# TiltyDuo.net
KiCad netlist of a schematic drawn in EAGLE
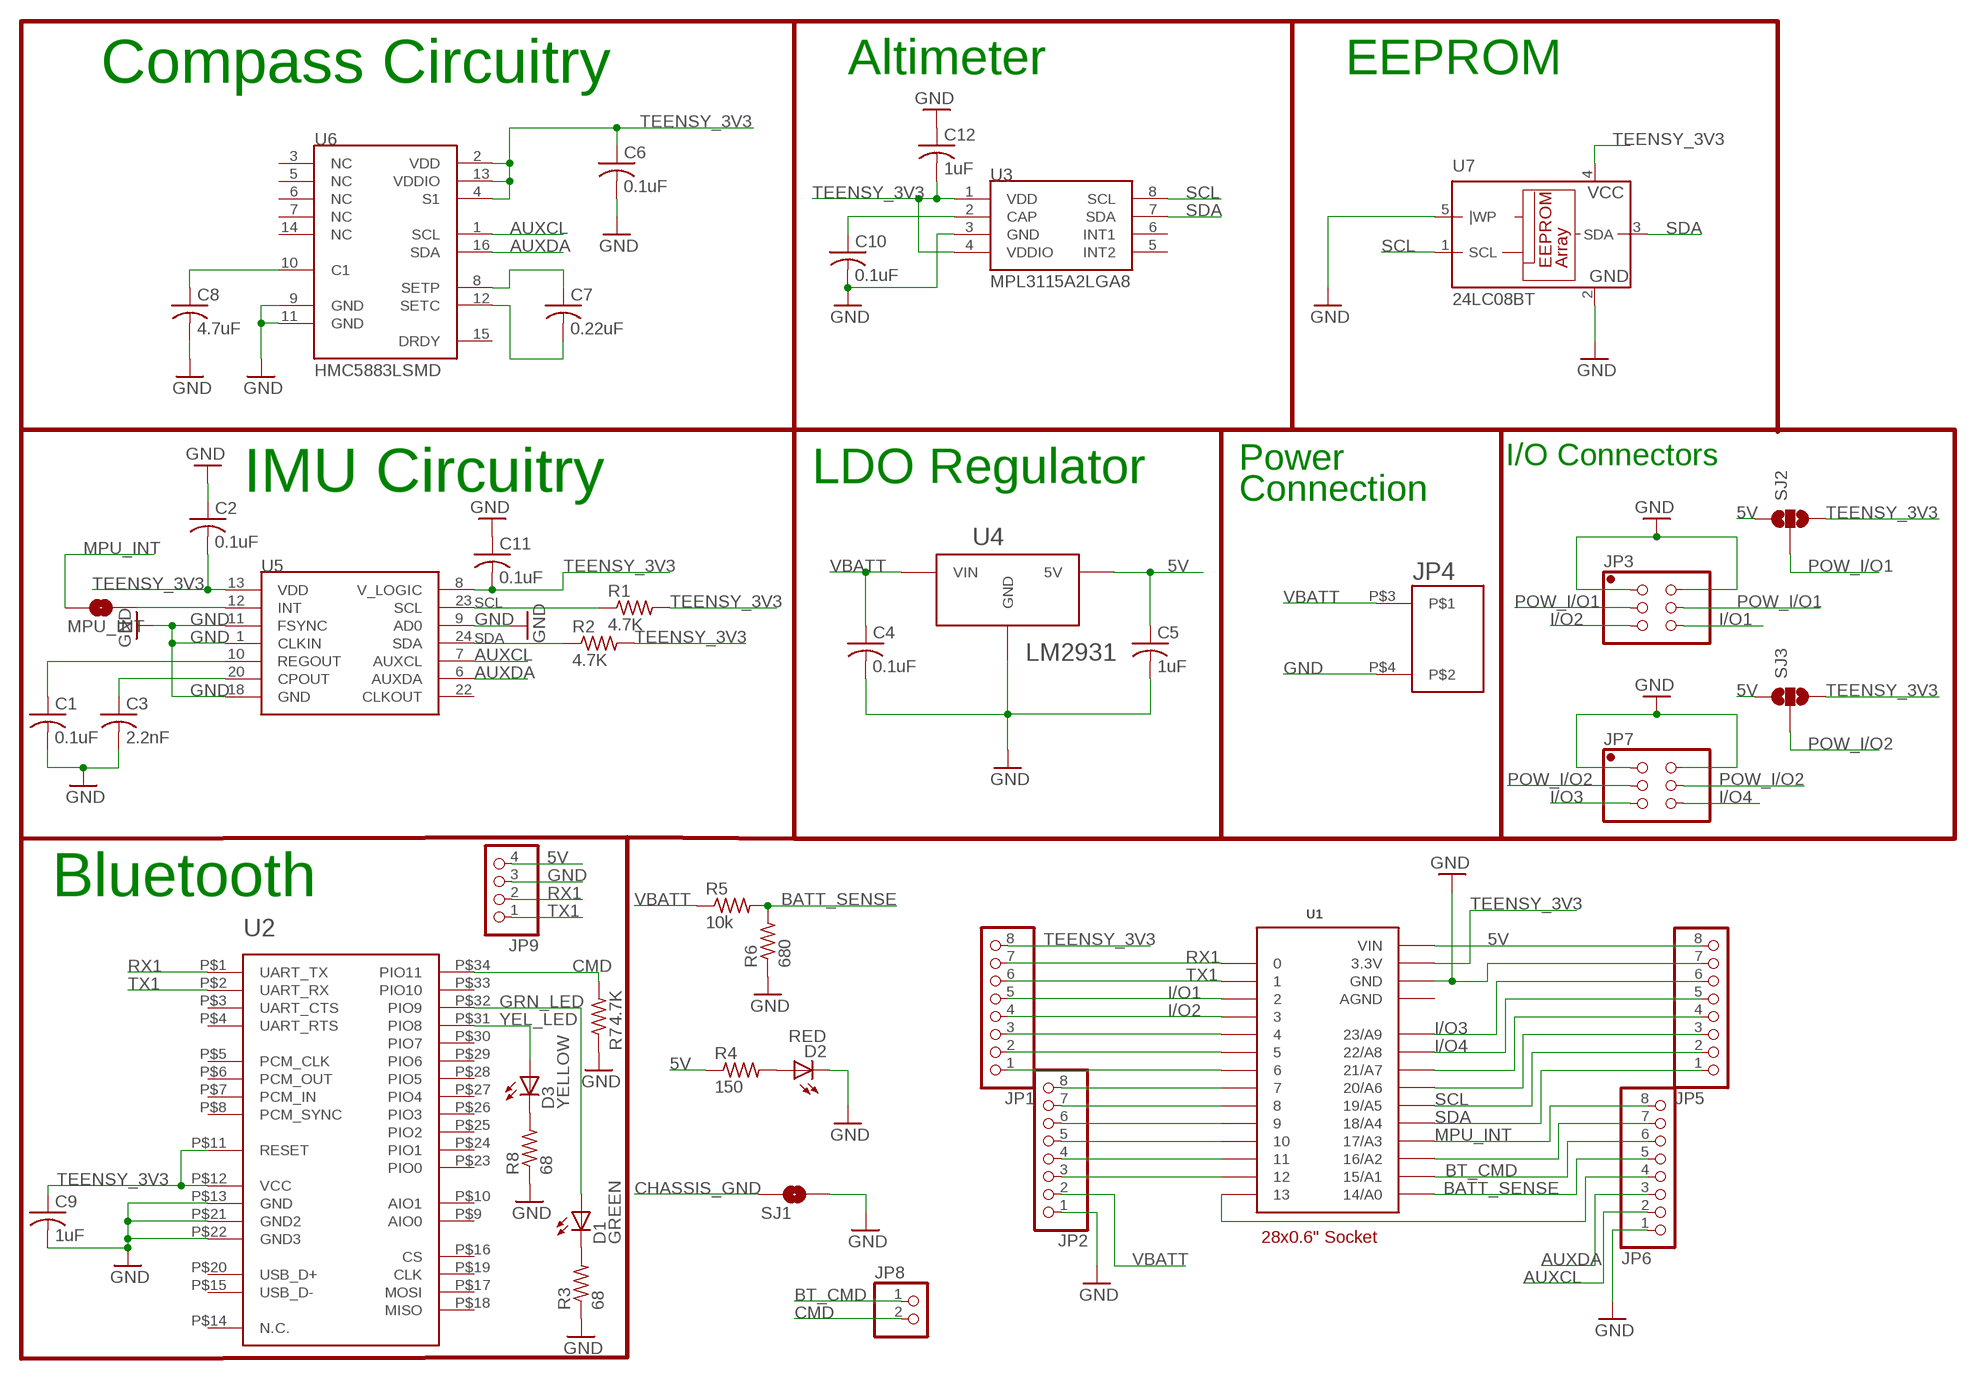
[diagram p0: schematic, sheet 1]

(export (version "E")
  (design (tool "Eeschema 10.0.6"))
  (components
    (comp (ref "C1")
      (value "0.1uF")
      (footprint "eagle-import:C0603")
      (libsource (lib "eagle-import") (part "C-USC0603"))
    )
    (comp (ref "C2")
      (value "0.1uF")
      (footprint "eagle-import:C0603")
      (libsource (lib "eagle-import") (part "C-USC0603"))
    )
    (comp (ref "C3")
      (value "2.2nF")
      (footprint "eagle-import:C0603")
      (libsource (lib "eagle-import") (part "C-USC0603"))
    )
    (comp (ref "C4")
      (value "0.1uF")
      (footprint "eagle-import:C0603")
      (libsource (lib "eagle-import") (part "C-USC0603"))
    )
    (comp (ref "C5")
      (value "1uF")
      (footprint "eagle-import:C0603")
      (libsource (lib "eagle-import") (part "C-USC0603"))
    )
    (comp (ref "C6")
      (value "0.1uF")
      (footprint "eagle-import:C0603")
      (libsource (lib "eagle-import") (part "C-USC0603"))
    )
    (comp (ref "C7")
      (value "0.22uF")
      (footprint "eagle-import:C0603")
      (libsource (lib "eagle-import") (part "C-USC0603"))
    )
    (comp (ref "C8")
      (value "4.7uF")
      (footprint "eagle-import:C0603")
      (libsource (lib "eagle-import") (part "C-USC0603"))
    )
    (comp (ref "C9")
      (value "1uF")
      (footprint "eagle-import:C0603")
      (libsource (lib "eagle-import") (part "C-USC0603"))
    )
    (comp (ref "C10")
      (value "0.1uF")
      (footprint "eagle-import:C0603")
      (libsource (lib "eagle-import") (part "C-USC0603"))
    )
    (comp (ref "C11")
      (value "0.1uF")
      (footprint "eagle-import:C0603")
      (libsource (lib "eagle-import") (part "C-USC0603"))
    )
    (comp (ref "C12")
      (value "1uF")
      (footprint "eagle-import:C0603")
      (libsource (lib "eagle-import") (part "C-USC0603"))
    )
    (comp (ref "D1")
      (value "GREEN")
      (footprint "eagle-import:LED-0805")
      (libsource (lib "eagle-import") (part "LED-GREENLED-0805_NO_SILK"))
    )
    (comp (ref "D2")
      (value "RED")
      (footprint "eagle-import:LED-0805")
      (libsource (lib "eagle-import") (part "LED-GREENLED-0805_NO_SILK"))
    )
    (comp (ref "D3")
      (value "YELLOW")
      (footprint "eagle-import:LED-0805")
      (libsource (lib "eagle-import") (part "LED-GREENLED-0805_NO_SILK"))
    )
    (comp (ref "JP1")
      (value "PINHD-1X81X08_NO_SILK")
      (footprint "eagle-import:1X08_NO_SS")
      (libsource (lib "eagle-import") (part "PINHD-1X81X08_NO_SILK"))
    )
    (comp (ref "JP2")
      (value "PINHD-1X81X08_NO_SILK")
      (footprint "eagle-import:1X08_NO_SS")
      (libsource (lib "eagle-import") (part "PINHD-1X81X08_NO_SILK"))
    )
    (comp (ref "JP3")
      (value "PINHD-2X32X03_NO_SILK")
      (footprint "eagle-import:2X03_NO_SS")
      (libsource (lib "eagle-import") (part "PINHD-2X32X03_NO_SILK"))
    )
    (comp (ref "JP4")
      (value "2-POS_SMD_TERM_BLOCK")
      (footprint "eagle-import:2-POS_SMD_TERMINAL_BLOCK")
      (libsource (lib "eagle-import") (part "2-POS_SMD_TERM_BLOCK"))
    )
    (comp (ref "JP5")
      (value "PINHD-1X81X08_NO_SILK")
      (footprint "eagle-import:1X08_NO_SS")
      (libsource (lib "eagle-import") (part "PINHD-1X81X08_NO_SILK"))
    )
    (comp (ref "JP6")
      (value "PINHD-1X81X08_NO_SILK")
      (footprint "eagle-import:1X08_NO_SS")
      (libsource (lib "eagle-import") (part "PINHD-1X81X08_NO_SILK"))
    )
    (comp (ref "JP7")
      (value "PINHD-2X32X03_NO_SILK")
      (footprint "eagle-import:2X03_NO_SS")
      (libsource (lib "eagle-import") (part "PINHD-2X32X03_NO_SILK"))
    )
    (comp (ref "JP8")
      (value "PINHD-1X21X02_NO_SILK")
      (footprint "eagle-import:1X02_NO_SS")
      (libsource (lib "eagle-import") (part "PINHD-1X21X02_NO_SILK"))
    )
    (comp (ref "JP9")
      (value "PINHD-1X4")
      (footprint "eagle-import:1X04")
      (libsource (lib "eagle-import") (part "PINHD-1X4"))
    )
    (comp (ref "MPU_INT")
      (value "SOLDERJUMPERNO")
      (footprint "eagle-import:SJ_2S-NO")
      (libsource (lib "eagle-import") (part "SOLDERJUMPERNO"))
    )
    (comp (ref "R1")
      (value "4.7K")
      (footprint "eagle-import:R0402")
      (libsource (lib "eagle-import") (part "R-US_R0402"))
    )
    (comp (ref "R2")
      (value "4.7K")
      (footprint "eagle-import:R0402")
      (libsource (lib "eagle-import") (part "R-US_R0402"))
    )
    (comp (ref "R3")
      (value "68")
      (footprint "eagle-import:R0603")
      (libsource (lib "eagle-import") (part "R-US_R0603"))
    )
    (comp (ref "R4")
      (value "150")
      (footprint "eagle-import:R0603")
      (libsource (lib "eagle-import") (part "R-US_R0603"))
    )
    (comp (ref "R5")
      (value "10k")
      (footprint "eagle-import:R0603")
      (libsource (lib "eagle-import") (part "R-US_R0603"))
    )
    (comp (ref "R6")
      (value "680")
      (footprint "eagle-import:R0603")
      (libsource (lib "eagle-import") (part "R-US_R0603"))
    )
    (comp (ref "R7")
      (value "4.7K")
      (footprint "eagle-import:R0603")
      (libsource (lib "eagle-import") (part "R-US_R0603"))
    )
    (comp (ref "R8")
      (value "68")
      (footprint "eagle-import:R0603")
      (libsource (lib "eagle-import") (part "R-US_R0603"))
    )
    (comp (ref "SJ1")
      (value "SOLDERJUMPERNO")
      (footprint "eagle-import:SJ_2S-NO")
      (libsource (lib "eagle-import") (part "SOLDERJUMPERNO"))
    )
    (comp (ref "SJ2")
      (value "SOLDERJUMPER_2WAYS")
      (footprint "eagle-import:SJ_3")
      (libsource (lib "eagle-import") (part "SOLDERJUMPER_2WAYS"))
    )
    (comp (ref "SJ3")
      (value "SOLDERJUMPER_2WAYS")
      (footprint "eagle-import:SJ_3")
      (libsource (lib "eagle-import") (part "SOLDERJUMPER_2WAYS"))
    )
    (comp (ref "U1")
      (value "TEENSY_3.0_OUTER-PINS28-DIP_SOCKET")
      (footprint "eagle-import:28-DIP")
      (libsource (lib "eagle-import") (part "TEENSY_3.0_OUTER-PINS28-DIP_SOCKET"))
    )
    (comp (ref "U2")
      (value "HC-09_BREAKOUT")
      (footprint "eagle-import:HC-09_BREAKOUT")
      (libsource (lib "eagle-import") (part "HC-09_BREAKOUT"))
    )
    (comp (ref "U3")
      (value "MPL3115A2LGA8")
      (footprint "eagle-import:LGA8")
      (libsource (lib "eagle-import") (part "MPL3115A2LGA8"))
    )
    (comp (ref "U4")
      (value "LM2931")
      (footprint "eagle-import:TO263")
      (libsource (lib "eagle-import") (part "LM2931"))
    )
    (comp (ref "U5")
      (value "MPU-6050")
      (footprint "eagle-import:QFN-24")
      (libsource (lib "eagle-import") (part "MPU-6050"))
    )
    (comp (ref "U6")
      (value "HMC5883LSMD")
      (footprint "eagle-import:16LPCC")
      (libsource (lib "eagle-import") (part "HMC5883LSMD"))
    )
    (comp (ref "U7")
      (value "24LC08BT")
      (footprint "eagle-import:SOT23-5L")
      (libsource (lib "eagle-import") (part "24LC08BT"))
    )
  )
  (nets
    (net (code "1") (name "/5V") (class "Default")
      (node (ref "C5") (pin "1") (pinfunction "1_1") (pintype "passive"))
      (node (ref "JP5") (pin "8") (pinfunction "8_8") (pintype "passive"))
      (node (ref "JP9") (pin "4") (pinfunction "4_4") (pintype "passive"))
      (node (ref "R4") (pin "1") (pinfunction "1_1") (pintype "passive"))
      (node (ref "SJ2") (pin "1") (pinfunction "1_1") (pintype "passive"))
      (node (ref "SJ3") (pin "1") (pinfunction "1_1") (pintype "passive"))
      (node (ref "U1") (pin "P$15") (pinfunction "VIN_P$15") (pintype "power_in"))
      (node (ref "U4") (pin "P$3") (pinfunction "5V_P$3") (pintype "bidirectional"))
    )
    (net (code "2") (name "/AGND") (class "Default")
      (node (ref "U1") (pin "P$16") (pinfunction "AGND_P$16") (pintype "power_in"))
    )
    (net (code "3") (name "/AUXCL") (class "Default")
      (node (ref "JP6") (pin "2") (pinfunction "2_2") (pintype "passive"))
      (node (ref "U5") (pin "7") (pinfunction "AUXCL_7") (pintype "bidirectional"))
      (node (ref "U6") (pin "1") (pinfunction "SCL_1") (pintype "bidirectional"))
    )
    (net (code "4") (name "/AUXDA") (class "Default")
      (node (ref "JP6") (pin "3") (pinfunction "3_3") (pintype "passive"))
      (node (ref "U5") (pin "6") (pinfunction "AUXDA_6") (pintype "bidirectional"))
      (node (ref "U6") (pin "16") (pinfunction "SDA_16") (pintype "bidirectional"))
    )
    (net (code "5") (name "/BATT_SENSE") (class "Default")
      (node (ref "JP6") (pin "5") (pinfunction "5_5") (pintype "passive"))
      (node (ref "R5") (pin "2") (pinfunction "2_2") (pintype "passive"))
      (node (ref "R6") (pin "2") (pinfunction "2_2") (pintype "passive"))
      (node (ref "U1") (pin "P$27") (pinfunction "14/A0_P$27") (pintype "bidirectional"))
    )
    (net (code "6") (name "/BT_CMD") (class "Default")
      (node (ref "JP6") (pin "6") (pinfunction "6_6") (pintype "passive"))
      (node (ref "JP8") (pin "1") (pinfunction "1_1") (pintype "passive"))
      (node (ref "U1") (pin "P$26") (pinfunction "15/A1_P$26") (pintype "bidirectional"))
    )
    (net (code "7") (name "/CHASSIS_GND") (class "Default")
      (node (ref "SJ1") (pin "1") (pinfunction "1_1") (pintype "passive"))
    )
    (net (code "8") (name "/CMD") (class "Default")
      (node (ref "JP8") (pin "2") (pinfunction "2_2") (pintype "passive"))
      (node (ref "R7") (pin "2") (pinfunction "2_2") (pintype "passive"))
      (node (ref "U2") (pin "P$34") (pinfunction "PIO11_P$34") (pintype "bidirectional"))
    )
    (net (code "9") (name "/GRN_LED") (class "Default")
      (node (ref "D1") (pin "1") (pinfunction "A_1") (pintype "passive"))
      (node (ref "U2") (pin "P$32") (pinfunction "PIO9_P$32") (pintype "bidirectional"))
    )
    (net (code "10") (name "/I{slash}O1") (class "Default")
      (node (ref "JP1") (pin "5") (pinfunction "5_5") (pintype "passive"))
      (node (ref "JP3") (pin "6") (pinfunction "6_6") (pintype "passive"))
      (node (ref "U1") (pin "P$4") (pinfunction "2_P$4") (pintype "bidirectional"))
    )
    (net (code "11") (name "/I{slash}O2") (class "Default")
      (node (ref "JP1") (pin "4") (pinfunction "4_4") (pintype "passive"))
      (node (ref "JP3") (pin "5") (pinfunction "5_5") (pintype "passive"))
      (node (ref "U1") (pin "P$5") (pinfunction "3_P$5") (pintype "bidirectional"))
    )
    (net (code "12") (name "/I{slash}O3") (class "Default")
      (node (ref "JP5") (pin "6") (pinfunction "6_6") (pintype "passive"))
      (node (ref "JP7") (pin "5") (pinfunction "5_5") (pintype "passive"))
      (node (ref "U1") (pin "P$18") (pinfunction "23/A9_P$18") (pintype "bidirectional"))
    )
    (net (code "13") (name "/I{slash}O4") (class "Default")
      (node (ref "JP5") (pin "5") (pinfunction "5_5") (pintype "passive"))
      (node (ref "JP7") (pin "6") (pinfunction "6_6") (pintype "passive"))
      (node (ref "U1") (pin "P$19") (pinfunction "22/A8_P$19") (pintype "bidirectional"))
    )
    (net (code "14") (name "/MPU_INT") (class "Default")
      (node (ref "JP6") (pin "8") (pinfunction "8_8") (pintype "passive"))
      (node (ref "MPU_INT") (pin "1") (pinfunction "1_1") (pintype "passive"))
      (node (ref "U1") (pin "P$24") (pinfunction "17/A3_P$24") (pintype "bidirectional"))
    )
    (net (code "15") (name "/POW_I{slash}O1") (class "Default")
      (node (ref "JP3") (pin "3") (pinfunction "3_3") (pintype "passive"))
      (node (ref "JP3") (pin "4") (pinfunction "4_4") (pintype "passive"))
      (node (ref "SJ2") (pin "2") (pinfunction "2_2") (pintype "passive"))
    )
    (net (code "16") (name "/POW_I{slash}O2") (class "Default")
      (node (ref "JP7") (pin "3") (pinfunction "3_3") (pintype "passive"))
      (node (ref "JP7") (pin "4") (pinfunction "4_4") (pintype "passive"))
      (node (ref "SJ3") (pin "2") (pinfunction "2_2") (pintype "passive"))
    )
    (net (code "17") (name "/RX1") (class "Default")
      (node (ref "JP1") (pin "7") (pinfunction "7_7") (pintype "passive"))
      (node (ref "JP9") (pin "2") (pinfunction "2_2") (pintype "passive"))
      (node (ref "U1") (pin "P$2") (pinfunction "0_P$2") (pintype "bidirectional"))
      (node (ref "U2") (pin "P$1") (pinfunction "UART_TX_P$1") (pintype "bidirectional"))
    )
    (net (code "18") (name "/SCL") (class "Default")
      (node (ref "JP5") (pin "2") (pinfunction "2_2") (pintype "passive"))
      (node (ref "R1") (pin "1") (pinfunction "1_1") (pintype "passive"))
      (node (ref "U1") (pin "P$22") (pinfunction "19/A5_P$22") (pintype "bidirectional"))
      (node (ref "U3") (pin "8") (pinfunction "SCL_8") (pintype "bidirectional"))
      (node (ref "U5") (pin "23") (pinfunction "SCL_23") (pintype "bidirectional"))
      (node (ref "U7") (pin "1") (pinfunction "SCL_1") (pintype "input"))
    )
    (net (code "19") (name "/SDA") (class "Default")
      (node (ref "JP5") (pin "1") (pinfunction "1_1") (pintype "passive"))
      (node (ref "R2") (pin "1") (pinfunction "1_1") (pintype "passive"))
      (node (ref "U1") (pin "P$23") (pinfunction "18/A4_P$23") (pintype "bidirectional"))
      (node (ref "U3") (pin "7") (pinfunction "SDA_7") (pintype "bidirectional"))
      (node (ref "U5") (pin "24") (pinfunction "SDA_24") (pintype "bidirectional"))
      (node (ref "U7") (pin "3") (pinfunction "SDA_3") (pintype "bidirectional"))
    )
    (net (code "20") (name "/TEENSY_3V3") (class "Default")
      (node (ref "C11") (pin "2") (pinfunction "2_2") (pintype "passive"))
      (node (ref "C12") (pin "2") (pinfunction "2_2") (pintype "passive"))
      (node (ref "C2") (pin "2") (pinfunction "2_2") (pintype "passive"))
      (node (ref "C6") (pin "1") (pinfunction "1_1") (pintype "passive"))
      (node (ref "C9") (pin "1") (pinfunction "1_1") (pintype "passive"))
      (node (ref "JP1") (pin "8") (pinfunction "8_8") (pintype "passive"))
      (node (ref "R1") (pin "2") (pinfunction "2_2") (pintype "passive"))
      (node (ref "R2") (pin "2") (pinfunction "2_2") (pintype "passive"))
      (node (ref "SJ2") (pin "3") (pinfunction "3_3") (pintype "passive"))
      (node (ref "SJ3") (pin "3") (pinfunction "3_3") (pintype "passive"))
      (node (ref "U1") (pin "P$17") (pinfunction "3.3V_P$17") (pintype "power_in"))
      (node (ref "U2") (pin "P$11") (pinfunction "RESET_P$11") (pintype "bidirectional"))
      (node (ref "U2") (pin "P$12") (pinfunction "VCC_P$12") (pintype "bidirectional"))
      (node (ref "U3") (pin "1") (pinfunction "VDD_1") (pintype "bidirectional"))
      (node (ref "U3") (pin "4") (pinfunction "VDDIO_4") (pintype "bidirectional"))
      (node (ref "U5") (pin "13") (pinfunction "VDD_13") (pintype "bidirectional"))
      (node (ref "U5") (pin "8") (pinfunction "V_LOGIC_8") (pintype "bidirectional"))
      (node (ref "U6") (pin "13") (pinfunction "VDDIO_13") (pintype "bidirectional"))
      (node (ref "U6") (pin "2") (pinfunction "VDD_2") (pintype "bidirectional"))
      (node (ref "U6") (pin "4") (pinfunction "S1_4") (pintype "bidirectional"))
      (node (ref "U7") (pin "4") (pinfunction "VCC_4") (pintype "power_in"))
    )
    (net (code "21") (name "/TX1") (class "Default")
      (node (ref "JP1") (pin "6") (pinfunction "6_6") (pintype "passive"))
      (node (ref "JP9") (pin "1") (pinfunction "1_1") (pintype "passive"))
      (node (ref "U1") (pin "P$3") (pinfunction "1_P$3") (pintype "bidirectional"))
      (node (ref "U2") (pin "P$2") (pinfunction "UART_RX_P$2") (pintype "bidirectional"))
    )
    (net (code "22") (name "/VBATT") (class "Default")
      (node (ref "C4") (pin "1") (pinfunction "1_1") (pintype "passive"))
      (node (ref "JP2") (pin "2") (pinfunction "2_2") (pintype "passive"))
      (node (ref "JP4") (pin "P$3") (pinfunction "P$1_P$3") (pintype "bidirectional"))
      (node (ref "R5") (pin "1") (pinfunction "1_1") (pintype "passive"))
      (node (ref "U4") (pin "P$2") (pinfunction "VIN_P$2") (pintype "bidirectional"))
    )
    (net (code "23") (name "/YEL_LED") (class "Default")
      (node (ref "D3") (pin "1") (pinfunction "A_1") (pintype "passive"))
      (node (ref "U2") (pin "P$31") (pinfunction "PIO8_P$31") (pintype "bidirectional"))
    )
    (net (code "24") (name "GND") (class "Default")
      (node (ref "C1") (pin "2") (pinfunction "2_2") (pintype "passive"))
      (node (ref "C10") (pin "2") (pinfunction "2_2") (pintype "passive"))
      (node (ref "C11") (pin "1") (pinfunction "1_1") (pintype "passive"))
      (node (ref "C12") (pin "1") (pinfunction "1_1") (pintype "passive"))
      (node (ref "C2") (pin "1") (pinfunction "1_1") (pintype "passive"))
      (node (ref "C3") (pin "2") (pinfunction "2_2") (pintype "passive"))
      (node (ref "C4") (pin "2") (pinfunction "2_2") (pintype "passive"))
      (node (ref "C5") (pin "2") (pinfunction "2_2") (pintype "passive"))
      (node (ref "C6") (pin "2") (pinfunction "2_2") (pintype "passive"))
      (node (ref "C8") (pin "2") (pinfunction "2_2") (pintype "passive"))
      (node (ref "C9") (pin "2") (pinfunction "2_2") (pintype "passive"))
      (node (ref "D2") (pin "2") (pinfunction "C_2") (pintype "passive"))
      (node (ref "JP2") (pin "1") (pinfunction "1_1") (pintype "passive"))
      (node (ref "JP3") (pin "1") (pinfunction "1_1") (pintype "passive"))
      (node (ref "JP3") (pin "2") (pinfunction "2_2") (pintype "passive"))
      (node (ref "JP4") (pin "P$4") (pinfunction "P$2_P$4") (pintype "bidirectional"))
      (node (ref "JP5") (pin "7") (pinfunction "7_7") (pintype "passive"))
      (node (ref "JP6") (pin "1") (pinfunction "1_1") (pintype "passive"))
      (node (ref "JP7") (pin "1") (pinfunction "1_1") (pintype "passive"))
      (node (ref "JP7") (pin "2") (pinfunction "2_2") (pintype "passive"))
      (node (ref "JP9") (pin "3") (pinfunction "3_3") (pintype "passive"))
      (node (ref "R3") (pin "1") (pinfunction "1_1") (pintype "passive"))
      (node (ref "R6") (pin "1") (pinfunction "1_1") (pintype "passive"))
      (node (ref "R7") (pin "1") (pinfunction "1_1") (pintype "passive"))
      (node (ref "R8") (pin "1") (pinfunction "1_1") (pintype "passive"))
      (node (ref "SJ1") (pin "2") (pinfunction "2_2") (pintype "passive"))
      (node (ref "U1") (pin "P$1") (pinfunction "GND_P$1") (pintype "power_in"))
      (node (ref "U2") (pin "P$13") (pinfunction "GND_P$13") (pintype "bidirectional"))
      (node (ref "U2") (pin "P$21") (pinfunction "GND2_P$21") (pintype "bidirectional"))
      (node (ref "U2") (pin "P$22") (pinfunction "GND3_P$22") (pintype "bidirectional"))
      (node (ref "U3") (pin "3") (pinfunction "GND_3") (pintype "bidirectional"))
      (node (ref "U4") (pin "P$1") (pinfunction "GND_P$1") (pintype "bidirectional"))
      (node (ref "U5") (pin "1") (pinfunction "CLKIN_1") (pintype "bidirectional"))
      (node (ref "U5") (pin "11") (pinfunction "FSYNC_11") (pintype "bidirectional"))
      (node (ref "U5") (pin "18") (pinfunction "GND_18") (pintype "bidirectional"))
      (node (ref "U5") (pin "9") (pinfunction "AD0_9") (pintype "bidirectional"))
      (node (ref "U6") (pin "11") (pinfunction "GND_11") (pintype "bidirectional"))
      (node (ref "U6") (pin "9") (pinfunction "GND_9") (pintype "bidirectional"))
      (node (ref "U7") (pin "2") (pinfunction "GND_2") (pintype "power_in"))
      (node (ref "U7") (pin "5") (pinfunction "|WP_5") (pintype "input"))
    )
    (net (code "25") (name "Net-(D1-C)") (class "Default")
      (node (ref "D1") (pin "2") (pinfunction "C_2") (pintype "passive"))
      (node (ref "R3") (pin "2") (pinfunction "2_2") (pintype "passive"))
    )
    (net (code "26") (name "Net-(D2-A)") (class "Default")
      (node (ref "D2") (pin "1") (pinfunction "A_1") (pintype "passive"))
      (node (ref "R4") (pin "2") (pinfunction "2_2") (pintype "passive"))
    )
    (net (code "27") (name "Net-(D3-C)") (class "Default")
      (node (ref "D3") (pin "2") (pinfunction "C_2") (pintype "passive"))
      (node (ref "R8") (pin "2") (pinfunction "2_2") (pintype "passive"))
    )
    (net (code "28") (name "Net-(U1-4)") (class "Default")
      (node (ref "JP1") (pin "3") (pinfunction "3_3") (pintype "passive"))
      (node (ref "U1") (pin "P$6") (pinfunction "4_P$6") (pintype "bidirectional"))
    )
    (net (code "29") (name "Net-(U1-5)") (class "Default")
      (node (ref "JP1") (pin "2") (pinfunction "2_2") (pintype "passive"))
      (node (ref "U1") (pin "P$7") (pinfunction "5_P$7") (pintype "bidirectional"))
    )
    (net (code "30") (name "Net-(U1-6)") (class "Default")
      (node (ref "JP1") (pin "1") (pinfunction "1_1") (pintype "passive"))
      (node (ref "U1") (pin "P$8") (pinfunction "6_P$8") (pintype "bidirectional"))
    )
    (net (code "31") (name "Net-(U1-7)") (class "Default")
      (node (ref "JP2") (pin "8") (pinfunction "8_8") (pintype "passive"))
      (node (ref "U1") (pin "P$9") (pinfunction "7_P$9") (pintype "bidirectional"))
    )
    (net (code "32") (name "Net-(U1-8)") (class "Default")
      (node (ref "JP2") (pin "7") (pinfunction "7_7") (pintype "passive"))
      (node (ref "U1") (pin "P$10") (pinfunction "8_P$10") (pintype "bidirectional"))
    )
    (net (code "33") (name "Net-(U1-9)") (class "Default")
      (node (ref "JP2") (pin "6") (pinfunction "6_6") (pintype "passive"))
      (node (ref "U1") (pin "P$11") (pinfunction "9_P$11") (pintype "bidirectional"))
    )
    (net (code "34") (name "Net-(U1-10)") (class "Default")
      (node (ref "JP2") (pin "5") (pinfunction "5_5") (pintype "passive"))
      (node (ref "U1") (pin "P$12") (pinfunction "10_P$12") (pintype "bidirectional"))
    )
    (net (code "35") (name "Net-(U1-11)") (class "Default")
      (node (ref "JP2") (pin "4") (pinfunction "4_4") (pintype "passive"))
      (node (ref "U1") (pin "P$13") (pinfunction "11_P$13") (pintype "bidirectional"))
    )
    (net (code "36") (name "Net-(U1-12)") (class "Default")
      (node (ref "JP2") (pin "3") (pinfunction "3_3") (pintype "passive"))
      (node (ref "U1") (pin "P$14") (pinfunction "12_P$14") (pintype "bidirectional"))
    )
    (net (code "37") (name "Net-(U1-13)") (class "Default")
      (node (ref "JP6") (pin "4") (pinfunction "4_4") (pintype "passive"))
      (node (ref "U1") (pin "P$28") (pinfunction "13_P$28") (pintype "bidirectional"))
    )
    (net (code "38") (name "Net-(U1-16{slash}A2)") (class "Default")
      (node (ref "JP6") (pin "7") (pinfunction "7_7") (pintype "passive"))
      (node (ref "U1") (pin "P$25") (pinfunction "16/A2_P$25") (pintype "bidirectional"))
    )
    (net (code "39") (name "Net-(U1-20{slash}A6)") (class "Default")
      (node (ref "JP5") (pin "3") (pinfunction "3_3") (pintype "passive"))
      (node (ref "U1") (pin "P$21") (pinfunction "20/A6_P$21") (pintype "bidirectional"))
    )
    (net (code "40") (name "Net-(U1-21{slash}A7)") (class "Default")
      (node (ref "JP5") (pin "4") (pinfunction "4_4") (pintype "passive"))
      (node (ref "U1") (pin "P$20") (pinfunction "21/A7_P$20") (pintype "bidirectional"))
    )
    (net (code "41") (name "Net-(U3-CAP)") (class "Default")
      (node (ref "C10") (pin "1") (pinfunction "1_1") (pintype "passive"))
      (node (ref "U3") (pin "2") (pinfunction "CAP_2") (pintype "bidirectional"))
    )
    (net (code "42") (name "Net-(U5-CPOUT)") (class "Default")
      (node (ref "C3") (pin "1") (pinfunction "1_1") (pintype "passive"))
      (node (ref "U5") (pin "20") (pinfunction "CPOUT_20") (pintype "bidirectional"))
    )
    (net (code "43") (name "Net-(U5-INT)") (class "Default")
      (node (ref "MPU_INT") (pin "2") (pinfunction "2_2") (pintype "passive"))
      (node (ref "U5") (pin "12") (pinfunction "INT_12") (pintype "bidirectional"))
    )
    (net (code "44") (name "Net-(U5-REGOUT)") (class "Default")
      (node (ref "C1") (pin "1") (pinfunction "1_1") (pintype "passive"))
      (node (ref "U5") (pin "10") (pinfunction "REGOUT_10") (pintype "bidirectional"))
    )
    (net (code "45") (name "Net-(U6-C1)") (class "Default")
      (node (ref "C8") (pin "1") (pinfunction "1_1") (pintype "passive"))
      (node (ref "U6") (pin "10") (pinfunction "C1_10") (pintype "bidirectional"))
    )
    (net (code "46") (name "Net-(U6-SETC)") (class "Default")
      (node (ref "C7") (pin "2") (pinfunction "2_2") (pintype "passive"))
      (node (ref "U6") (pin "12") (pinfunction "SETC_12") (pintype "bidirectional"))
    )
    (net (code "47") (name "Net-(U6-SETP)") (class "Default")
      (node (ref "C7") (pin "1") (pinfunction "1_1") (pintype "passive"))
      (node (ref "U6") (pin "8") (pinfunction "SETP_8") (pintype "bidirectional"))
    )
    (net (code "48") (name "unconnected-(U2-AIO0-PadP$9)") (class "Default")
      (node (ref "U2") (pin "P$9") (pinfunction "AIO0_P$9") (pintype "bidirectional"))
    )
    (net (code "49") (name "unconnected-(U2-AIO1-PadP$10)") (class "Default")
      (node (ref "U2") (pin "P$10") (pinfunction "AIO1_P$10") (pintype "bidirectional"))
    )
    (net (code "50") (name "unconnected-(U2-CLK-PadP$19)") (class "Default")
      (node (ref "U2") (pin "P$19") (pinfunction "CLK_P$19") (pintype "bidirectional"))
    )
    (net (code "51") (name "unconnected-(U2-CS-PadP$16)") (class "Default")
      (node (ref "U2") (pin "P$16") (pinfunction "CS_P$16") (pintype "bidirectional"))
    )
    (net (code "52") (name "unconnected-(U2-MISO-PadP$18)") (class "Default")
      (node (ref "U2") (pin "P$18") (pinfunction "MISO_P$18") (pintype "bidirectional"))
    )
    (net (code "53") (name "unconnected-(U2-MOSI-PadP$17)") (class "Default")
      (node (ref "U2") (pin "P$17") (pinfunction "MOSI_P$17") (pintype "bidirectional"))
    )
    (net (code "54") (name "unconnected-(U2-N.C.-PadP$14)") (class "Default")
      (node (ref "U2") (pin "P$14") (pinfunction "N.C._P$14") (pintype "bidirectional"))
    )
    (net (code "55") (name "unconnected-(U2-PCM_CLK-PadP$5)") (class "Default")
      (node (ref "U2") (pin "P$5") (pinfunction "PCM_CLK_P$5") (pintype "bidirectional"))
    )
    (net (code "56") (name "unconnected-(U2-PCM_IN-PadP$7)") (class "Default")
      (node (ref "U2") (pin "P$7") (pinfunction "PCM_IN_P$7") (pintype "bidirectional"))
    )
    (net (code "57") (name "unconnected-(U2-PCM_OUT-PadP$6)") (class "Default")
      (node (ref "U2") (pin "P$6") (pinfunction "PCM_OUT_P$6") (pintype "bidirectional"))
    )
    (net (code "58") (name "unconnected-(U2-PCM_SYNC-PadP$8)") (class "Default")
      (node (ref "U2") (pin "P$8") (pinfunction "PCM_SYNC_P$8") (pintype "bidirectional"))
    )
    (net (code "59") (name "unconnected-(U2-PIO0-PadP$23)") (class "Default")
      (node (ref "U2") (pin "P$23") (pinfunction "PIO0_P$23") (pintype "bidirectional"))
    )
    (net (code "60") (name "unconnected-(U2-PIO1-PadP$24)") (class "Default")
      (node (ref "U2") (pin "P$24") (pinfunction "PIO1_P$24") (pintype "bidirectional"))
    )
    (net (code "61") (name "unconnected-(U2-PIO2-PadP$25)") (class "Default")
      (node (ref "U2") (pin "P$25") (pinfunction "PIO2_P$25") (pintype "bidirectional"))
    )
    (net (code "62") (name "unconnected-(U2-PIO3-PadP$26)") (class "Default")
      (node (ref "U2") (pin "P$26") (pinfunction "PIO3_P$26") (pintype "bidirectional"))
    )
    (net (code "63") (name "unconnected-(U2-PIO4-PadP$27)") (class "Default")
      (node (ref "U2") (pin "P$27") (pinfunction "PIO4_P$27") (pintype "bidirectional"))
    )
    (net (code "64") (name "unconnected-(U2-PIO5-PadP$28)") (class "Default")
      (node (ref "U2") (pin "P$28") (pinfunction "PIO5_P$28") (pintype "bidirectional"))
    )
    (net (code "65") (name "unconnected-(U2-PIO6-PadP$29)") (class "Default")
      (node (ref "U2") (pin "P$29") (pinfunction "PIO6_P$29") (pintype "bidirectional"))
    )
    (net (code "66") (name "unconnected-(U2-PIO7-PadP$30)") (class "Default")
      (node (ref "U2") (pin "P$30") (pinfunction "PIO7_P$30") (pintype "bidirectional"))
    )
    (net (code "67") (name "unconnected-(U2-PIO10-PadP$33)") (class "Default")
      (node (ref "U2") (pin "P$33") (pinfunction "PIO10_P$33") (pintype "bidirectional"))
    )
    (net (code "68") (name "unconnected-(U2-UART_CTS-PadP$3)") (class "Default")
      (node (ref "U2") (pin "P$3") (pinfunction "UART_CTS_P$3") (pintype "bidirectional"))
    )
    (net (code "69") (name "unconnected-(U2-UART_RTS-PadP$4)") (class "Default")
      (node (ref "U2") (pin "P$4") (pinfunction "UART_RTS_P$4") (pintype "bidirectional"))
    )
    (net (code "70") (name "unconnected-(U2-USB_D+-PadP$20)") (class "Default")
      (node (ref "U2") (pin "P$20") (pinfunction "USB_D+_P$20") (pintype "bidirectional"))
    )
    (net (code "71") (name "unconnected-(U2-USB_D--PadP$15)") (class "Default")
      (node (ref "U2") (pin "P$15") (pinfunction "USB_D-_P$15") (pintype "bidirectional"))
    )
    (net (code "72") (name "unconnected-(U3-INT1-Pad6)") (class "Default")
      (node (ref "U3") (pin "6") (pinfunction "INT1_6") (pintype "bidirectional"))
    )
    (net (code "73") (name "unconnected-(U3-INT2-Pad5)") (class "Default")
      (node (ref "U3") (pin "5") (pinfunction "INT2_5") (pintype "bidirectional"))
    )
    (net (code "74") (name "unconnected-(U5-CLKOUT-Pad22)") (class "Default")
      (node (ref "U5") (pin "22") (pinfunction "CLKOUT_22") (pintype "bidirectional"))
    )
    (net (code "75") (name "unconnected-(U6-DRDY-Pad15)") (class "Default")
      (node (ref "U6") (pin "15") (pinfunction "DRDY_15") (pintype "bidirectional"))
    )
    (net (code "76") (name "unconnected-(U6-NC-Pad3)") (class "Default")
      (node (ref "U6") (pin "3") (pinfunction "NC_3") (pintype "bidirectional"))
    )
    (net (code "77") (name "unconnected-(U6-NC-Pad5)") (class "Default")
      (node (ref "U6") (pin "5") (pinfunction "NC_5") (pintype "bidirectional"))
    )
    (net (code "78") (name "unconnected-(U6-NC-Pad6)") (class "Default")
      (node (ref "U6") (pin "6") (pinfunction "NC_6") (pintype "bidirectional"))
    )
    (net (code "79") (name "unconnected-(U6-NC-Pad7)") (class "Default")
      (node (ref "U6") (pin "7") (pinfunction "NC_7") (pintype "bidirectional"))
    )
    (net (code "80") (name "unconnected-(U6-NC-Pad14)") (class "Default")
      (node (ref "U6") (pin "14") (pinfunction "NC_14") (pintype "bidirectional"))
    )
  )
)
